# ATX_12V_Switching.net
KiCad netlist of a schematic drawn in EAGLE
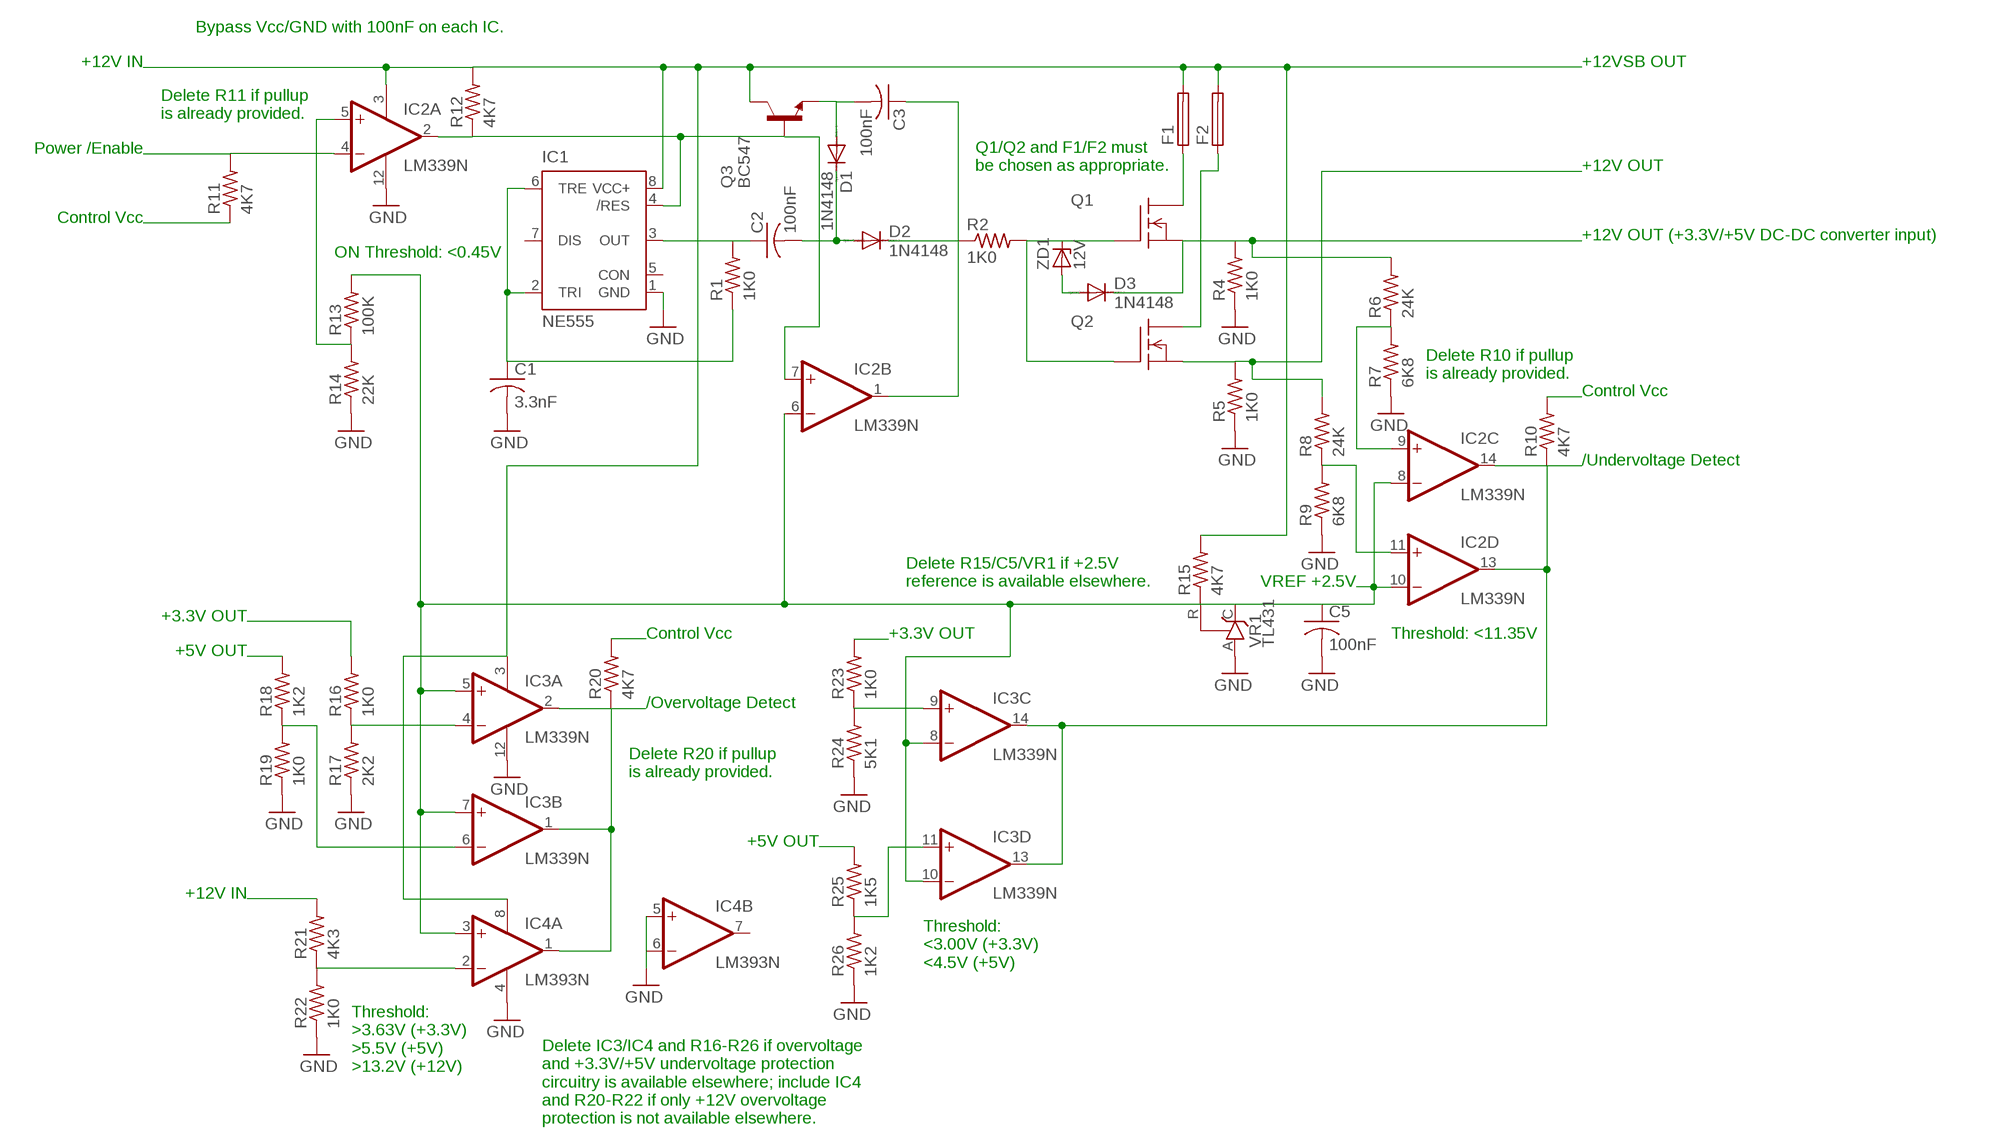
[diagram p0: schematic, sheet 1]

(export (version "E")
  (design (tool "Eeschema 10.0.6"))
  (components
    (comp (ref "C1")
      (value "3.3nF")
      (footprint "eagle-import:C025-024X044")
      (libsource (lib "eagle-import") (part "C-US025-024X044"))
    )
    (comp (ref "C2")
      (value "100nF")
      (footprint "eagle-import:C025-024X044")
      (libsource (lib "eagle-import") (part "C-US025-024X044"))
    )
    (comp (ref "C3")
      (value "100nF")
      (footprint "eagle-import:C025-024X044")
      (libsource (lib "eagle-import") (part "C-US025-024X044"))
    )
    (comp (ref "C5")
      (value "100nF")
      (footprint "eagle-import:C025-024X044")
      (libsource (lib "eagle-import") (part "C-US025-024X044"))
    )
    (comp (ref "D1")
      (value "1N4148")
      (footprint "eagle-import:DO35-7")
      (libsource (lib "eagle-import") (part "1N4148DO35-7"))
    )
    (comp (ref "D2")
      (value "1N4148")
      (footprint "eagle-import:DO35-7")
      (libsource (lib "eagle-import") (part "1N4148DO35-7"))
    )
    (comp (ref "D3")
      (value "1N4148")
      (footprint "eagle-import:DO35-7")
      (libsource (lib "eagle-import") (part "1N4148DO35-7"))
    )
    (comp (ref "F1")
      (value "19559")
      (footprint "eagle-import:19559")
      (fields (field (name "MPN") "55900000001"))
      (libsource (lib "eagle-import") (part "19559"))
    )
    (comp (ref "F2")
      (value "19559")
      (footprint "eagle-import:19559")
      (fields (field (name "MPN") "55900000001"))
      (libsource (lib "eagle-import") (part "19559"))
    )
    (comp (ref "IC1")
      (value "NE555")
      (footprint "eagle-import:DIL-08")
      (fields (field (name "MF") "Arrow Electronics") (field (name "MPN") "NE555N"))
      (libsource (lib "eagle-import") (part "NE555"))
    )
    (comp (ref "IC2")
      (value "LM339N")
      (footprint "eagle-import:DIL14")
      (libsource (lib "eagle-import") (part "LM339N"))
    )
    (comp (ref "IC3")
      (value "LM339N")
      (footprint "eagle-import:DIL14")
      (libsource (lib "eagle-import") (part "LM339N"))
    )
    (comp (ref "IC4")
      (value "LM393N")
      (footprint "eagle-import:DIL08")
      (libsource (lib "eagle-import") (part "LM393N"))
    )
    (comp (ref "Q1")
      (value "BUZ10")
      (footprint "eagle-import:TO220")
      (libsource (lib "eagle-import") (part "BUZ10"))
    )
    (comp (ref "Q2")
      (value "BUZ10")
      (footprint "eagle-import:TO220")
      (libsource (lib "eagle-import") (part "BUZ10"))
    )
    (comp (ref "Q3")
      (value "BC547")
      (footprint "eagle-import:TO92")
      (libsource (lib "eagle-import") (part "BC547"))
    )
    (comp (ref "R1")
      (value "1K0")
      (footprint "eagle-import:0204V")
      (libsource (lib "eagle-import") (part "R-US_0204/2V"))
    )
    (comp (ref "R2")
      (value "1K0")
      (footprint "eagle-import:0204V")
      (libsource (lib "eagle-import") (part "R-US_0204/2V"))
    )
    (comp (ref "R4")
      (value "1K0")
      (footprint "eagle-import:0204V")
      (libsource (lib "eagle-import") (part "R-US_0204/2V"))
    )
    (comp (ref "R5")
      (value "1K0")
      (footprint "eagle-import:0204V")
      (libsource (lib "eagle-import") (part "R-US_0204/2V"))
    )
    (comp (ref "R6")
      (value "24K")
      (footprint "eagle-import:0204V")
      (libsource (lib "eagle-import") (part "R-US_0204/2V"))
    )
    (comp (ref "R7")
      (value "6K8")
      (footprint "eagle-import:0204V")
      (libsource (lib "eagle-import") (part "R-US_0204/2V"))
    )
    (comp (ref "R8")
      (value "24K")
      (footprint "eagle-import:0204V")
      (libsource (lib "eagle-import") (part "R-US_0204/2V"))
    )
    (comp (ref "R9")
      (value "6K8")
      (footprint "eagle-import:0204V")
      (libsource (lib "eagle-import") (part "R-US_0204/2V"))
    )
    (comp (ref "R10")
      (value "4K7")
      (footprint "eagle-import:0204V")
      (libsource (lib "eagle-import") (part "R-US_0204/2V"))
    )
    (comp (ref "R11")
      (value "4K7")
      (footprint "eagle-import:0204V")
      (libsource (lib "eagle-import") (part "R-US_0204/2V"))
    )
    (comp (ref "R12")
      (value "4K7")
      (footprint "eagle-import:0204V")
      (libsource (lib "eagle-import") (part "R-US_0204/2V"))
    )
    (comp (ref "R13")
      (value "100K")
      (footprint "eagle-import:0204V")
      (libsource (lib "eagle-import") (part "R-US_0204/2V"))
    )
    (comp (ref "R14")
      (value "22K")
      (footprint "eagle-import:0204V")
      (libsource (lib "eagle-import") (part "R-US_0204/2V"))
    )
    (comp (ref "R15")
      (value "4K7")
      (footprint "eagle-import:0204V")
      (libsource (lib "eagle-import") (part "R-US_0204/2V"))
    )
    (comp (ref "R16")
      (value "1K0")
      (footprint "eagle-import:0204V")
      (libsource (lib "eagle-import") (part "R-US_0204/2V"))
    )
    (comp (ref "R17")
      (value "2K2")
      (footprint "eagle-import:0204V")
      (libsource (lib "eagle-import") (part "R-US_0204/2V"))
    )
    (comp (ref "R18")
      (value "1K2")
      (footprint "eagle-import:0204V")
      (libsource (lib "eagle-import") (part "R-US_0204/2V"))
    )
    (comp (ref "R19")
      (value "1K0")
      (footprint "eagle-import:0204V")
      (libsource (lib "eagle-import") (part "R-US_0204/2V"))
    )
    (comp (ref "R20")
      (value "4K7")
      (footprint "eagle-import:0204V")
      (libsource (lib "eagle-import") (part "R-US_0204/2V"))
    )
    (comp (ref "R21")
      (value "4K3")
      (footprint "eagle-import:0204V")
      (libsource (lib "eagle-import") (part "R-US_0204/2V"))
    )
    (comp (ref "R22")
      (value "1K0")
      (footprint "eagle-import:0204V")
      (libsource (lib "eagle-import") (part "R-US_0204/2V"))
    )
    (comp (ref "R23")
      (value "1K0")
      (footprint "eagle-import:0204V")
      (libsource (lib "eagle-import") (part "R-US_0204/2V"))
    )
    (comp (ref "R24")
      (value "5K1")
      (footprint "eagle-import:0204V")
      (libsource (lib "eagle-import") (part "R-US_0204/2V"))
    )
    (comp (ref "R25")
      (value "1K5")
      (footprint "eagle-import:0204V")
      (libsource (lib "eagle-import") (part "R-US_0204/2V"))
    )
    (comp (ref "R26")
      (value "1K2")
      (footprint "eagle-import:0204V")
      (libsource (lib "eagle-import") (part "R-US_0204/2V"))
    )
    (comp (ref "VR1")
      (value "TL431")
      (footprint "eagle-import:TO92-CLP")
      (libsource (lib "eagle-import") (part "TL431CLP"))
    )
    (comp (ref "ZD1")
      (value "12V")
      (footprint "eagle-import:C1702-15")
      (libsource (lib "eagle-import") (part "ZENER-DIODEC1702-15"))
    )
  )
  (nets
    (net (code "1") (name "GND") (class "Default")
      (node (ref "C1") (pin "2") (pinfunction "2_2") (pintype "passive"))
      (node (ref "C5") (pin "2") (pinfunction "2_2") (pintype "passive"))
      (node (ref "IC1") (pin "1") (pinfunction "GND_1") (pintype "power_in"))
      (node (ref "IC2") (pin "12") (pinfunction "GND_12") (pintype "power_in"))
      (node (ref "IC3") (pin "12") (pinfunction "GND_12") (pintype "power_in"))
      (node (ref "IC4") (pin "4") (pinfunction "V-_4") (pintype "power_in"))
      (node (ref "IC4") (pin "5") (pinfunction "+IN_5") (pintype "input"))
      (node (ref "IC4") (pin "6") (pinfunction "-IN_6") (pintype "input"))
      (node (ref "R14") (pin "1") (pinfunction "1_1") (pintype "passive"))
      (node (ref "R17") (pin "1") (pinfunction "1_1") (pintype "passive"))
      (node (ref "R19") (pin "1") (pinfunction "1_1") (pintype "passive"))
      (node (ref "R22") (pin "1") (pinfunction "1_1") (pintype "passive"))
      (node (ref "R24") (pin "1") (pinfunction "1_1") (pintype "passive"))
      (node (ref "R26") (pin "1") (pinfunction "1_1") (pintype "passive"))
      (node (ref "R4") (pin "1") (pinfunction "1_1") (pintype "passive"))
      (node (ref "R5") (pin "1") (pinfunction "1_1") (pintype "passive"))
      (node (ref "R7") (pin "1") (pinfunction "1_1") (pintype "passive"))
      (node (ref "R9") (pin "1") (pinfunction "1_1") (pintype "passive"))
      (node (ref "VR1") (pin "A") (pinfunction "A_A") (pintype "passive"))
    )
    (net (code "2") (name "Net-(C2-Pad2)") (class "Default")
      (node (ref "C2") (pin "2") (pinfunction "2_2") (pintype "passive"))
      (node (ref "D1") (pin "C") (pinfunction "C_C") (pintype "passive"))
      (node (ref "D2") (pin "A") (pinfunction "A_A") (pintype "passive"))
    )
    (net (code "3") (name "Net-(D3-PadA)") (class "Default")
      (node (ref "D3") (pin "A") (pinfunction "A_A") (pintype "passive"))
      (node (ref "ZD1") (pin "A") (pinfunction "A_A") (pintype "passive"))
    )
    (net (code "4") (name "Net-(IC1-OUT)") (class "Default")
      (node (ref "C2") (pin "1") (pinfunction "1_1") (pintype "passive"))
      (node (ref "IC1") (pin "3") (pinfunction "OUT_3") (pintype "output"))
      (node (ref "R1") (pin "2") (pinfunction "2_2") (pintype "passive"))
    )
    (net (code "5") (name "Net-(IC1-TRE)") (class "Default")
      (node (ref "C1") (pin "1") (pinfunction "1_1") (pintype "passive"))
      (node (ref "IC1") (pin "2") (pinfunction "TRI_2") (pintype "input"))
      (node (ref "IC1") (pin "6") (pinfunction "TRE_6") (pintype "input"))
      (node (ref "R1") (pin "1") (pinfunction "1_1") (pintype "passive"))
    )
    (net (code "6") (name "Net-(IC1-VCC+)") (class "Default")
      (node (ref "F1") (pin "2") (pinfunction "2_2") (pintype "passive"))
      (node (ref "F2") (pin "2") (pinfunction "2_2") (pintype "passive"))
      (node (ref "IC1") (pin "8") (pinfunction "VCC+_8") (pintype "power_in"))
      (node (ref "IC2") (pin "3") (pinfunction "V+_3") (pintype "power_in"))
      (node (ref "IC3") (pin "3") (pinfunction "V+_3") (pintype "power_in"))
      (node (ref "IC4") (pin "8") (pinfunction "V+_8") (pintype "power_in"))
      (node (ref "Q3") (pin "3") (pinfunction "C_3") (pintype "passive"))
      (node (ref "R12") (pin "2") (pinfunction "2_2") (pintype "passive"))
      (node (ref "R15") (pin "2") (pinfunction "2_2") (pintype "passive"))
    )
    (net (code "7") (name "Net-(IC1-{slash}RES)") (class "Default")
      (node (ref "IC1") (pin "4") (pinfunction "/RES_4") (pintype "input"))
      (node (ref "IC2") (pin "2") (pinfunction "OUT_2") (pintype "open_collector"))
      (node (ref "IC2") (pin "7") (pinfunction "+IN_7") (pintype "input"))
      (node (ref "Q3") (pin "2") (pinfunction "B_2") (pintype "passive"))
      (node (ref "R12") (pin "1") (pinfunction "1_1") (pintype "passive"))
    )
    (net (code "8") (name "Net-(IC2A-+IN)") (class "Default")
      (node (ref "IC2") (pin "5") (pinfunction "+IN_5") (pintype "input"))
      (node (ref "R13") (pin "1") (pinfunction "1_1") (pintype "passive"))
      (node (ref "R14") (pin "2") (pinfunction "2_2") (pintype "passive"))
    )
    (net (code "9") (name "Net-(IC2A--IN)") (class "Default")
      (node (ref "IC2") (pin "4") (pinfunction "-IN_4") (pintype "input"))
      (node (ref "R11") (pin "2") (pinfunction "2_2") (pintype "passive"))
    )
    (net (code "10") (name "Net-(IC2B--IN)") (class "Default")
      (node (ref "C5") (pin "1") (pinfunction "1_1") (pintype "passive"))
      (node (ref "IC2") (pin "10") (pinfunction "-IN_10") (pintype "input"))
      (node (ref "IC2") (pin "6") (pinfunction "-IN_6") (pintype "input"))
      (node (ref "IC2") (pin "8") (pinfunction "-IN_8") (pintype "input"))
      (node (ref "IC3") (pin "10") (pinfunction "-IN_10") (pintype "input"))
      (node (ref "IC3") (pin "5") (pinfunction "+IN_5") (pintype "input"))
      (node (ref "IC3") (pin "7") (pinfunction "+IN_7") (pintype "input"))
      (node (ref "IC3") (pin "8") (pinfunction "-IN_8") (pintype "input"))
      (node (ref "IC4") (pin "3") (pinfunction "+IN_3") (pintype "input"))
      (node (ref "R13") (pin "2") (pinfunction "2_2") (pintype "passive"))
      (node (ref "R15") (pin "1") (pinfunction "1_1") (pintype "passive"))
      (node (ref "VR1") (pin "C") (pinfunction "C_C") (pintype "passive"))
      (node (ref "VR1") (pin "R") (pinfunction "R_R") (pintype "passive"))
    )
    (net (code "11") (name "Net-(IC2B-OUT)") (class "Default")
      (node (ref "C3") (pin "1") (pinfunction "1_1") (pintype "passive"))
      (node (ref "D2") (pin "C") (pinfunction "C_C") (pintype "passive"))
      (node (ref "IC2") (pin "1") (pinfunction "OUT_1") (pintype "open_collector"))
      (node (ref "R2") (pin "1") (pinfunction "1_1") (pintype "passive"))
    )
    (net (code "12") (name "Net-(IC2C-+IN)") (class "Default")
      (node (ref "IC2") (pin "9") (pinfunction "+IN_9") (pintype "input"))
      (node (ref "R6") (pin "1") (pinfunction "1_1") (pintype "passive"))
      (node (ref "R7") (pin "2") (pinfunction "2_2") (pintype "passive"))
    )
    (net (code "13") (name "Net-(IC2C-OUT)") (class "Default")
      (node (ref "IC2") (pin "13") (pinfunction "OUT_13") (pintype "open_collector"))
      (node (ref "IC2") (pin "14") (pinfunction "OUT_14") (pintype "open_collector"))
      (node (ref "IC3") (pin "13") (pinfunction "OUT_13") (pintype "open_collector"))
      (node (ref "IC3") (pin "14") (pinfunction "OUT_14") (pintype "open_collector"))
      (node (ref "R10") (pin "1") (pinfunction "1_1") (pintype "passive"))
    )
    (net (code "14") (name "Net-(IC2D-+IN)") (class "Default")
      (node (ref "IC2") (pin "11") (pinfunction "+IN_11") (pintype "input"))
      (node (ref "R8") (pin "1") (pinfunction "1_1") (pintype "passive"))
      (node (ref "R9") (pin "2") (pinfunction "2_2") (pintype "passive"))
    )
    (net (code "15") (name "Net-(IC3A--IN)") (class "Default")
      (node (ref "IC3") (pin "4") (pinfunction "-IN_4") (pintype "input"))
      (node (ref "R16") (pin "1") (pinfunction "1_1") (pintype "passive"))
      (node (ref "R17") (pin "2") (pinfunction "2_2") (pintype "passive"))
    )
    (net (code "16") (name "Net-(IC3A-OUT)") (class "Default")
      (node (ref "IC3") (pin "1") (pinfunction "OUT_1") (pintype "open_collector"))
      (node (ref "IC3") (pin "2") (pinfunction "OUT_2") (pintype "open_collector"))
      (node (ref "IC4") (pin "1") (pinfunction "OUT_1") (pintype "output"))
      (node (ref "R20") (pin "1") (pinfunction "1_1") (pintype "passive"))
    )
    (net (code "17") (name "Net-(IC3B--IN)") (class "Default")
      (node (ref "IC3") (pin "6") (pinfunction "-IN_6") (pintype "input"))
      (node (ref "R18") (pin "1") (pinfunction "1_1") (pintype "passive"))
      (node (ref "R19") (pin "2") (pinfunction "2_2") (pintype "passive"))
    )
    (net (code "18") (name "Net-(IC3C-+IN)") (class "Default")
      (node (ref "IC3") (pin "9") (pinfunction "+IN_9") (pintype "input"))
      (node (ref "R23") (pin "1") (pinfunction "1_1") (pintype "passive"))
      (node (ref "R24") (pin "2") (pinfunction "2_2") (pintype "passive"))
    )
    (net (code "19") (name "Net-(IC3D-+IN)") (class "Default")
      (node (ref "IC3") (pin "11") (pinfunction "+IN_11") (pintype "input"))
      (node (ref "R25") (pin "1") (pinfunction "1_1") (pintype "passive"))
      (node (ref "R26") (pin "2") (pinfunction "2_2") (pintype "passive"))
    )
    (net (code "20") (name "Net-(IC4A--IN)") (class "Default")
      (node (ref "IC4") (pin "2") (pinfunction "-IN_2") (pintype "input"))
      (node (ref "R21") (pin "1") (pinfunction "1_1") (pintype "passive"))
      (node (ref "R22") (pin "2") (pinfunction "2_2") (pintype "passive"))
    )
    (net (code "21") (name "Net-(Q1-D)") (class "Default")
      (node (ref "F1") (pin "1") (pinfunction "1_1") (pintype "passive"))
      (node (ref "Q1") (pin "2") (pinfunction "D_2") (pintype "passive"))
    )
    (net (code "22") (name "Net-(Q1-G)") (class "Default")
      (node (ref "Q1") (pin "1") (pinfunction "G_1") (pintype "passive"))
      (node (ref "Q2") (pin "1") (pinfunction "G_1") (pintype "passive"))
      (node (ref "R2") (pin "2") (pinfunction "2_2") (pintype "passive"))
      (node (ref "ZD1") (pin "C") (pinfunction "C_C") (pintype "passive"))
    )
    (net (code "23") (name "Net-(Q1-S)") (class "Default")
      (node (ref "D3") (pin "C") (pinfunction "C_C") (pintype "passive"))
      (node (ref "Q1") (pin "3") (pinfunction "S_3") (pintype "passive"))
      (node (ref "R4") (pin "2") (pinfunction "2_2") (pintype "passive"))
      (node (ref "R6") (pin "2") (pinfunction "2_2") (pintype "passive"))
    )
    (net (code "24") (name "Net-(Q2-D)") (class "Default")
      (node (ref "F2") (pin "1") (pinfunction "1_1") (pintype "passive"))
      (node (ref "Q2") (pin "2") (pinfunction "D_2") (pintype "passive"))
    )
    (net (code "25") (name "Net-(Q2-S)") (class "Default")
      (node (ref "Q2") (pin "3") (pinfunction "S_3") (pintype "passive"))
      (node (ref "R5") (pin "2") (pinfunction "2_2") (pintype "passive"))
      (node (ref "R8") (pin "2") (pinfunction "2_2") (pintype "passive"))
    )
    (net (code "26") (name "Net-(Q3-E)") (class "Default")
      (node (ref "C3") (pin "2") (pinfunction "2_2") (pintype "passive"))
      (node (ref "D1") (pin "A") (pinfunction "A_A") (pintype "passive"))
      (node (ref "Q3") (pin "1") (pinfunction "E_1") (pintype "passive"))
    )
    (net (code "27") (name "unconnected-(IC1-CON-Pad5)") (class "Default")
      (node (ref "IC1") (pin "5") (pinfunction "CON_5") (pintype "input"))
    )
    (net (code "28") (name "unconnected-(IC1-DIS-Pad7)") (class "Default")
      (node (ref "IC1") (pin "7") (pinfunction "DIS_7") (pintype "input"))
    )
    (net (code "29") (name "unconnected-(IC4B-OUT-Pad7)") (class "Default")
      (node (ref "IC4") (pin "7") (pinfunction "OUT_7") (pintype "output"))
    )
    (net (code "30") (name "unconnected-(R10-Pad2)") (class "Default")
      (node (ref "R10") (pin "2") (pinfunction "2_2") (pintype "passive"))
    )
    (net (code "31") (name "unconnected-(R11-Pad1)") (class "Default")
      (node (ref "R11") (pin "1") (pinfunction "1_1") (pintype "passive"))
    )
    (net (code "32") (name "unconnected-(R16-Pad2)") (class "Default")
      (node (ref "R16") (pin "2") (pinfunction "2_2") (pintype "passive"))
    )
    (net (code "33") (name "unconnected-(R18-Pad2)") (class "Default")
      (node (ref "R18") (pin "2") (pinfunction "2_2") (pintype "passive"))
    )
    (net (code "34") (name "unconnected-(R20-Pad2)") (class "Default")
      (node (ref "R20") (pin "2") (pinfunction "2_2") (pintype "passive"))
    )
    (net (code "35") (name "unconnected-(R21-Pad2)") (class "Default")
      (node (ref "R21") (pin "2") (pinfunction "2_2") (pintype "passive"))
    )
    (net (code "36") (name "unconnected-(R23-Pad2)") (class "Default")
      (node (ref "R23") (pin "2") (pinfunction "2_2") (pintype "passive"))
    )
    (net (code "37") (name "unconnected-(R25-Pad2)") (class "Default")
      (node (ref "R25") (pin "2") (pinfunction "2_2") (pintype "passive"))
    )
  )
)
